# DCDC-17V12V5A.net
KiCad netlist of a schematic drawn in EAGLE
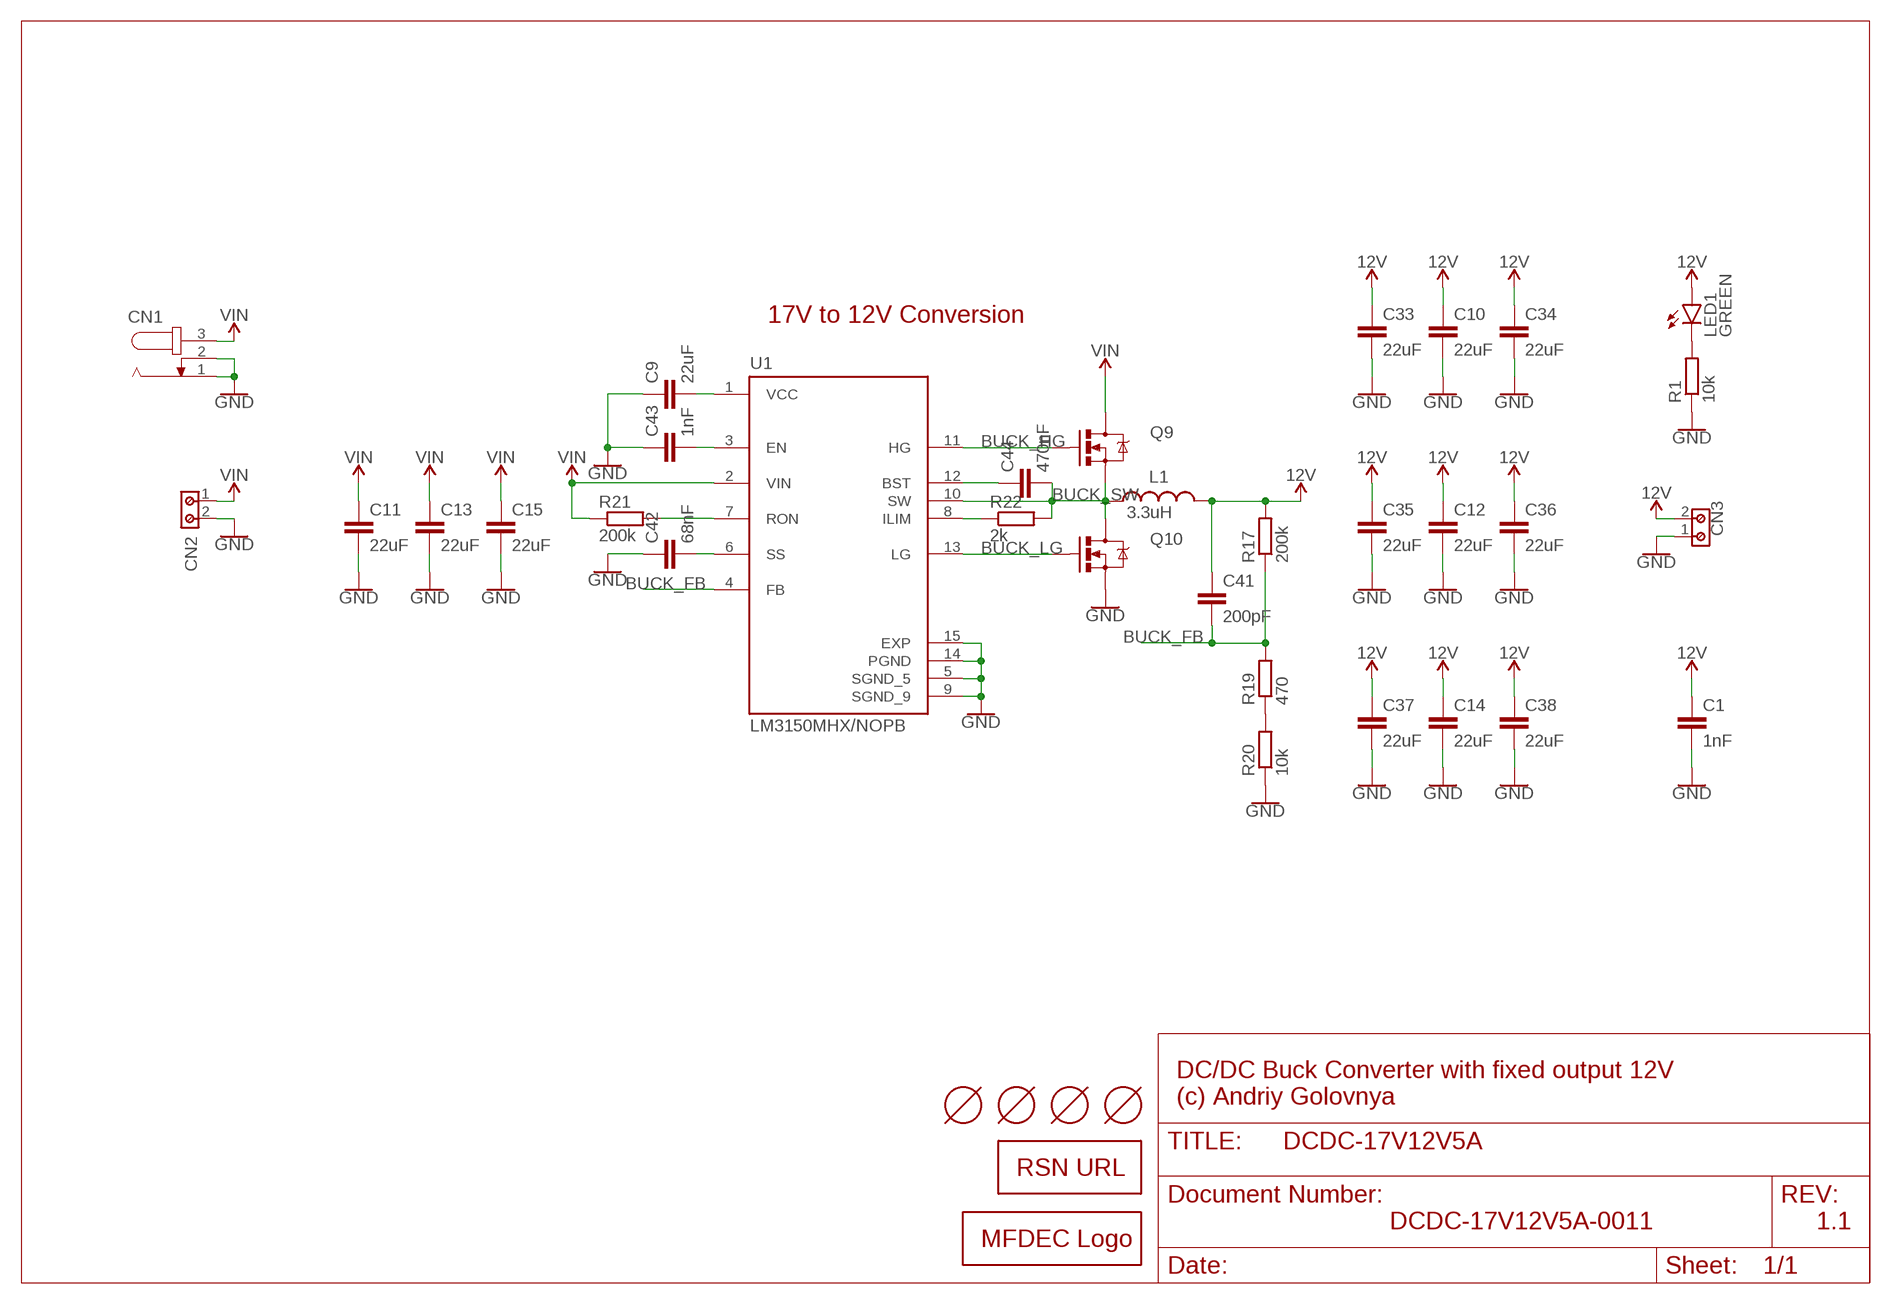
[diagram p0: schematic, sheet 1]

(export (version "E")
  (design (tool "Eeschema 10.0.6"))
  (components
    (comp (ref "C1")
      (value "1nF")
      (footprint "eagle-import:C0603K")
      (libsource (lib "eagle-import") (part "C-EUC0603K"))
    )
    (comp (ref "C9")
      (value "22uF")
      (footprint "eagle-import:C0805K")
      (libsource (lib "eagle-import") (part "C-EUC0805K"))
    )
    (comp (ref "C10")
      (value "22uF")
      (footprint "eagle-import:C0805K")
      (libsource (lib "eagle-import") (part "C-EUC0805K"))
    )
    (comp (ref "C11")
      (value "22uF")
      (footprint "eagle-import:C0805K")
      (libsource (lib "eagle-import") (part "C-EUC0805K"))
    )
    (comp (ref "C12")
      (value "22uF")
      (footprint "eagle-import:C0805K")
      (libsource (lib "eagle-import") (part "C-EUC0805K"))
    )
    (comp (ref "C13")
      (value "22uF")
      (footprint "eagle-import:C0805K")
      (libsource (lib "eagle-import") (part "C-EUC0805K"))
    )
    (comp (ref "C14")
      (value "22uF")
      (footprint "eagle-import:C0805K")
      (libsource (lib "eagle-import") (part "C-EUC0805K"))
    )
    (comp (ref "C15")
      (value "22uF")
      (footprint "eagle-import:C0805K")
      (libsource (lib "eagle-import") (part "C-EUC0805K"))
    )
    (comp (ref "C33")
      (value "22uF")
      (footprint "eagle-import:C0805K")
      (libsource (lib "eagle-import") (part "C-EUC0805K"))
    )
    (comp (ref "C34")
      (value "22uF")
      (footprint "eagle-import:C0805K")
      (libsource (lib "eagle-import") (part "C-EUC0805K"))
    )
    (comp (ref "C35")
      (value "22uF")
      (footprint "eagle-import:C0805K")
      (libsource (lib "eagle-import") (part "C-EUC0805K"))
    )
    (comp (ref "C36")
      (value "22uF")
      (footprint "eagle-import:C0805K")
      (libsource (lib "eagle-import") (part "C-EUC0805K"))
    )
    (comp (ref "C37")
      (value "22uF")
      (footprint "eagle-import:C0805K")
      (libsource (lib "eagle-import") (part "C-EUC0805K"))
    )
    (comp (ref "C38")
      (value "22uF")
      (footprint "eagle-import:C0805K")
      (libsource (lib "eagle-import") (part "C-EUC0805K"))
    )
    (comp (ref "C41")
      (value "200pF")
      (footprint "eagle-import:C0603K")
      (libsource (lib "eagle-import") (part "C-EUC0603K"))
    )
    (comp (ref "C42")
      (value "68nF")
      (footprint "eagle-import:C0603K")
      (libsource (lib "eagle-import") (part "C-EUC0603K"))
    )
    (comp (ref "C43")
      (value "1nF")
      (footprint "eagle-import:C0603K")
      (libsource (lib "eagle-import") (part "C-EUC0603K"))
    )
    (comp (ref "C44")
      (value "470nF")
      (footprint "eagle-import:C0603K")
      (libsource (lib "eagle-import") (part "C-EUC0603K"))
    )
    (comp (ref "CN1")
      (value "JACK-PLUG1")
      (footprint "eagle-import:SPC4078")
      (libsource (lib "eagle-import") (part "JACK-PLUG1"))
    )
    (comp (ref "CN2")
      (value "691213510002")
      (footprint "eagle-import:691213510002")
      (libsource (lib "eagle-import") (part "691213510002"))
    )
    (comp (ref "CN3")
      (value "691213510002")
      (footprint "eagle-import:691213510002")
      (libsource (lib "eagle-import") (part "691213510002"))
    )
    (comp (ref "HOLE1")
      (value "TOOLINGHOLE")
      (footprint "eagle-import:TOOLING-HOLE")
      (libsource (lib "eagle-import") (part "TOOLINGHOLE"))
    )
    (comp (ref "HOLE2")
      (value "TOOLINGHOLE")
      (footprint "eagle-import:TOOLING-HOLE")
      (libsource (lib "eagle-import") (part "TOOLINGHOLE"))
    )
    (comp (ref "HOLE3")
      (value "TOOLINGHOLE")
      (footprint "eagle-import:TOOLING-HOLE")
      (libsource (lib "eagle-import") (part "TOOLINGHOLE"))
    )
    (comp (ref "HOLE4")
      (value "TOOLINGHOLE")
      (footprint "eagle-import:TOOLING-HOLE")
      (libsource (lib "eagle-import") (part "TOOLINGHOLE"))
    )
    (comp (ref "L1")
      (value "3.3uH")
      (footprint "eagle-import:WE-CHSA_1011")
      (libsource (lib "eagle-import") (part "WE-CHSA_1011_7843330330"))
    )
    (comp (ref "LED1")
      (value "GREEN")
      (footprint "eagle-import:SML0603")
      (libsource (lib "eagle-import") (part "LEDSML0603"))
    )
    (comp (ref "LOGO1")
      (value "RSNURL_QR_8MM")
      (footprint "eagle-import:RSNURL_QR_8MM")
      (libsource (lib "eagle-import") (part "RSNURL_QR_8MM"))
    )
    (comp (ref "LOGO2")
      (value "MFDECLOGO_L_10MM")
      (footprint "eagle-import:MFDEC_L_10MM")
      (libsource (lib "eagle-import") (part "MFDECLOGO_L_10MM"))
    )
    (comp (ref "Q9")
      (value "NMOSFET")
      (footprint "eagle-import:DPAK")
      (libsource (lib "eagle-import") (part "MOSFET-NCHANNELFDD8780"))
    )
    (comp (ref "Q10")
      (value "NMOSFET")
      (footprint "eagle-import:DPAK")
      (libsource (lib "eagle-import") (part "MOSFET-NCHANNELFDD8780"))
    )
    (comp (ref "R1")
      (value "10k")
      (footprint "eagle-import:R0603")
      (libsource (lib "eagle-import") (part "R-EU_R0603"))
    )
    (comp (ref "R17")
      (value "200k")
      (footprint "eagle-import:R0603")
      (libsource (lib "eagle-import") (part "R-EU_R0603"))
    )
    (comp (ref "R19")
      (value "470")
      (footprint "eagle-import:R0603")
      (libsource (lib "eagle-import") (part "R-EU_R0603"))
    )
    (comp (ref "R20")
      (value "10k")
      (footprint "eagle-import:R0603")
      (libsource (lib "eagle-import") (part "R-EU_R0603"))
    )
    (comp (ref "R21")
      (value "200k")
      (footprint "eagle-import:R0603")
      (libsource (lib "eagle-import") (part "R-EU_R0603"))
    )
    (comp (ref "R22")
      (value "2k")
      (footprint "eagle-import:R0603")
      (libsource (lib "eagle-import") (part "R-EU_R0603"))
    )
    (comp (ref "U1")
      (value "LM3150MHX/NOPB")
      (footprint "eagle-import:SOP65P640X110-15N")
      (fields (field (name "MF") "Texas Instruments"))
      (libsource (lib "eagle-import") (part "LM3150MHX/NOPB"))
    )
  )
  (nets
    (net (code "1") (name "/BUCK_FB") (class "Default")
      (node (ref "C41") (pin "2") (pinfunction "2_2") (pintype "passive"))
      (node (ref "R17") (pin "1") (pinfunction "1_1") (pintype "passive"))
      (node (ref "R19") (pin "2") (pinfunction "2_2") (pintype "passive"))
      (node (ref "U1") (pin "4") (pinfunction "FB_4") (pintype "input"))
    )
    (net (code "2") (name "/BUCK_HG") (class "Default")
      (node (ref "Q9") (pin "1") (pinfunction "G_1") (pintype "passive"))
      (node (ref "U1") (pin "11") (pinfunction "HG_11") (pintype "output"))
    )
    (net (code "3") (name "/BUCK_LG") (class "Default")
      (node (ref "Q10") (pin "1") (pinfunction "G_1") (pintype "passive"))
      (node (ref "U1") (pin "13") (pinfunction "LG_13") (pintype "output"))
    )
    (net (code "4") (name "/BUCK_SW") (class "Default")
      (node (ref "C44") (pin "2") (pinfunction "2_2") (pintype "passive"))
      (node (ref "L1") (pin "1") (pinfunction "1_1") (pintype "passive"))
      (node (ref "Q10") (pin "4") (pinfunction "D_4") (pintype "passive"))
      (node (ref "Q9") (pin "3") (pinfunction "S_3") (pintype "passive"))
      (node (ref "R22") (pin "2") (pinfunction "2_2") (pintype "passive"))
      (node (ref "U1") (pin "10") (pinfunction "SW_10") (pintype "output"))
    )
    (net (code "5") (name "12V") (class "Default")
      (node (ref "C1") (pin "1") (pinfunction "1_1") (pintype "passive"))
      (node (ref "C10") (pin "1") (pinfunction "1_1") (pintype "passive"))
      (node (ref "C12") (pin "1") (pinfunction "1_1") (pintype "passive"))
      (node (ref "C14") (pin "1") (pinfunction "1_1") (pintype "passive"))
      (node (ref "C33") (pin "1") (pinfunction "1_1") (pintype "passive"))
      (node (ref "C34") (pin "1") (pinfunction "1_1") (pintype "passive"))
      (node (ref "C35") (pin "1") (pinfunction "1_1") (pintype "passive"))
      (node (ref "C36") (pin "1") (pinfunction "1_1") (pintype "passive"))
      (node (ref "C37") (pin "1") (pinfunction "1_1") (pintype "passive"))
      (node (ref "C38") (pin "1") (pinfunction "1_1") (pintype "passive"))
      (node (ref "C41") (pin "1") (pinfunction "1_1") (pintype "passive"))
      (node (ref "CN3") (pin "2") (pinfunction "2_2") (pintype "passive"))
      (node (ref "L1") (pin "2") (pinfunction "2_2") (pintype "passive"))
      (node (ref "LED1") (pin "A") (pinfunction "A_A") (pintype "passive"))
      (node (ref "R17") (pin "2") (pinfunction "2_2") (pintype "passive"))
    )
    (net (code "6") (name "GND") (class "Default")
      (node (ref "C1") (pin "2") (pinfunction "2_2") (pintype "passive"))
      (node (ref "C10") (pin "2") (pinfunction "2_2") (pintype "passive"))
      (node (ref "C11") (pin "2") (pinfunction "2_2") (pintype "passive"))
      (node (ref "C12") (pin "2") (pinfunction "2_2") (pintype "passive"))
      (node (ref "C13") (pin "2") (pinfunction "2_2") (pintype "passive"))
      (node (ref "C14") (pin "2") (pinfunction "2_2") (pintype "passive"))
      (node (ref "C15") (pin "2") (pinfunction "2_2") (pintype "passive"))
      (node (ref "C33") (pin "2") (pinfunction "2_2") (pintype "passive"))
      (node (ref "C34") (pin "2") (pinfunction "2_2") (pintype "passive"))
      (node (ref "C35") (pin "2") (pinfunction "2_2") (pintype "passive"))
      (node (ref "C36") (pin "2") (pinfunction "2_2") (pintype "passive"))
      (node (ref "C37") (pin "2") (pinfunction "2_2") (pintype "passive"))
      (node (ref "C38") (pin "2") (pinfunction "2_2") (pintype "passive"))
      (node (ref "C42") (pin "1") (pinfunction "1_1") (pintype "passive"))
      (node (ref "C43") (pin "1") (pinfunction "1_1") (pintype "passive"))
      (node (ref "C9") (pin "1") (pinfunction "1_1") (pintype "passive"))
      (node (ref "CN1") (pin "1") (pinfunction "1_1") (pintype "passive"))
      (node (ref "CN1") (pin "2") (pinfunction "2_2") (pintype "passive"))
      (node (ref "CN2") (pin "2") (pinfunction "2_2") (pintype "passive"))
      (node (ref "CN3") (pin "1") (pinfunction "1_1") (pintype "passive"))
      (node (ref "Q10") (pin "3") (pinfunction "S_3") (pintype "passive"))
      (node (ref "R1") (pin "1") (pinfunction "1_1") (pintype "passive"))
      (node (ref "R20") (pin "1") (pinfunction "1_1") (pintype "passive"))
      (node (ref "U1") (pin "14") (pinfunction "PGND_14") (pintype "power_in"))
      (node (ref "U1") (pin "15") (pinfunction "EXP_15") (pintype "power_in"))
      (node (ref "U1") (pin "5") (pinfunction "SGND_5_5") (pintype "power_in"))
      (node (ref "U1") (pin "9") (pinfunction "SGND_9_9") (pintype "power_in"))
    )
    (net (code "7") (name "Net-(LED1-PadC)") (class "Default")
      (node (ref "LED1") (pin "C") (pinfunction "C_C") (pintype "passive"))
      (node (ref "R1") (pin "2") (pinfunction "2_2") (pintype "passive"))
    )
    (net (code "8") (name "Net-(R19-Pad1)") (class "Default")
      (node (ref "R19") (pin "1") (pinfunction "1_1") (pintype "passive"))
      (node (ref "R20") (pin "2") (pinfunction "2_2") (pintype "passive"))
    )
    (net (code "9") (name "Net-(U1-BST)") (class "Default")
      (node (ref "C44") (pin "1") (pinfunction "1_1") (pintype "passive"))
      (node (ref "U1") (pin "12") (pinfunction "BST_12") (pintype "passive"))
    )
    (net (code "10") (name "Net-(U1-EN)") (class "Default")
      (node (ref "C43") (pin "2") (pinfunction "2_2") (pintype "passive"))
      (node (ref "U1") (pin "3") (pinfunction "EN_3") (pintype "input"))
    )
    (net (code "11") (name "Net-(U1-ILIM)") (class "Default")
      (node (ref "R22") (pin "1") (pinfunction "1_1") (pintype "passive"))
      (node (ref "U1") (pin "8") (pinfunction "ILIM_8") (pintype "passive"))
    )
    (net (code "12") (name "Net-(U1-RON)") (class "Default")
      (node (ref "R21") (pin "2") (pinfunction "2_2") (pintype "passive"))
      (node (ref "U1") (pin "7") (pinfunction "RON_7") (pintype "input"))
    )
    (net (code "13") (name "Net-(U1-SS)") (class "Default")
      (node (ref "C42") (pin "2") (pinfunction "2_2") (pintype "passive"))
      (node (ref "U1") (pin "6") (pinfunction "SS_6") (pintype "input"))
    )
    (net (code "14") (name "Net-(U1-VCC)") (class "Default")
      (node (ref "C9") (pin "2") (pinfunction "2_2") (pintype "passive"))
      (node (ref "U1") (pin "1") (pinfunction "VCC_1") (pintype "power_in"))
    )
    (net (code "15") (name "VIN") (class "Default")
      (node (ref "C11") (pin "1") (pinfunction "1_1") (pintype "passive"))
      (node (ref "C13") (pin "1") (pinfunction "1_1") (pintype "passive"))
      (node (ref "C15") (pin "1") (pinfunction "1_1") (pintype "passive"))
      (node (ref "CN1") (pin "3") (pinfunction "3_3") (pintype "passive"))
      (node (ref "CN2") (pin "1") (pinfunction "1_1") (pintype "passive"))
      (node (ref "Q9") (pin "4") (pinfunction "D_4") (pintype "passive"))
      (node (ref "R21") (pin "1") (pinfunction "1_1") (pintype "passive"))
      (node (ref "U1") (pin "2") (pinfunction "VIN_2") (pintype "input"))
    )
  )
)
